# signal_interface2.net
KiCad netlist of a schematic drawn in EAGLE
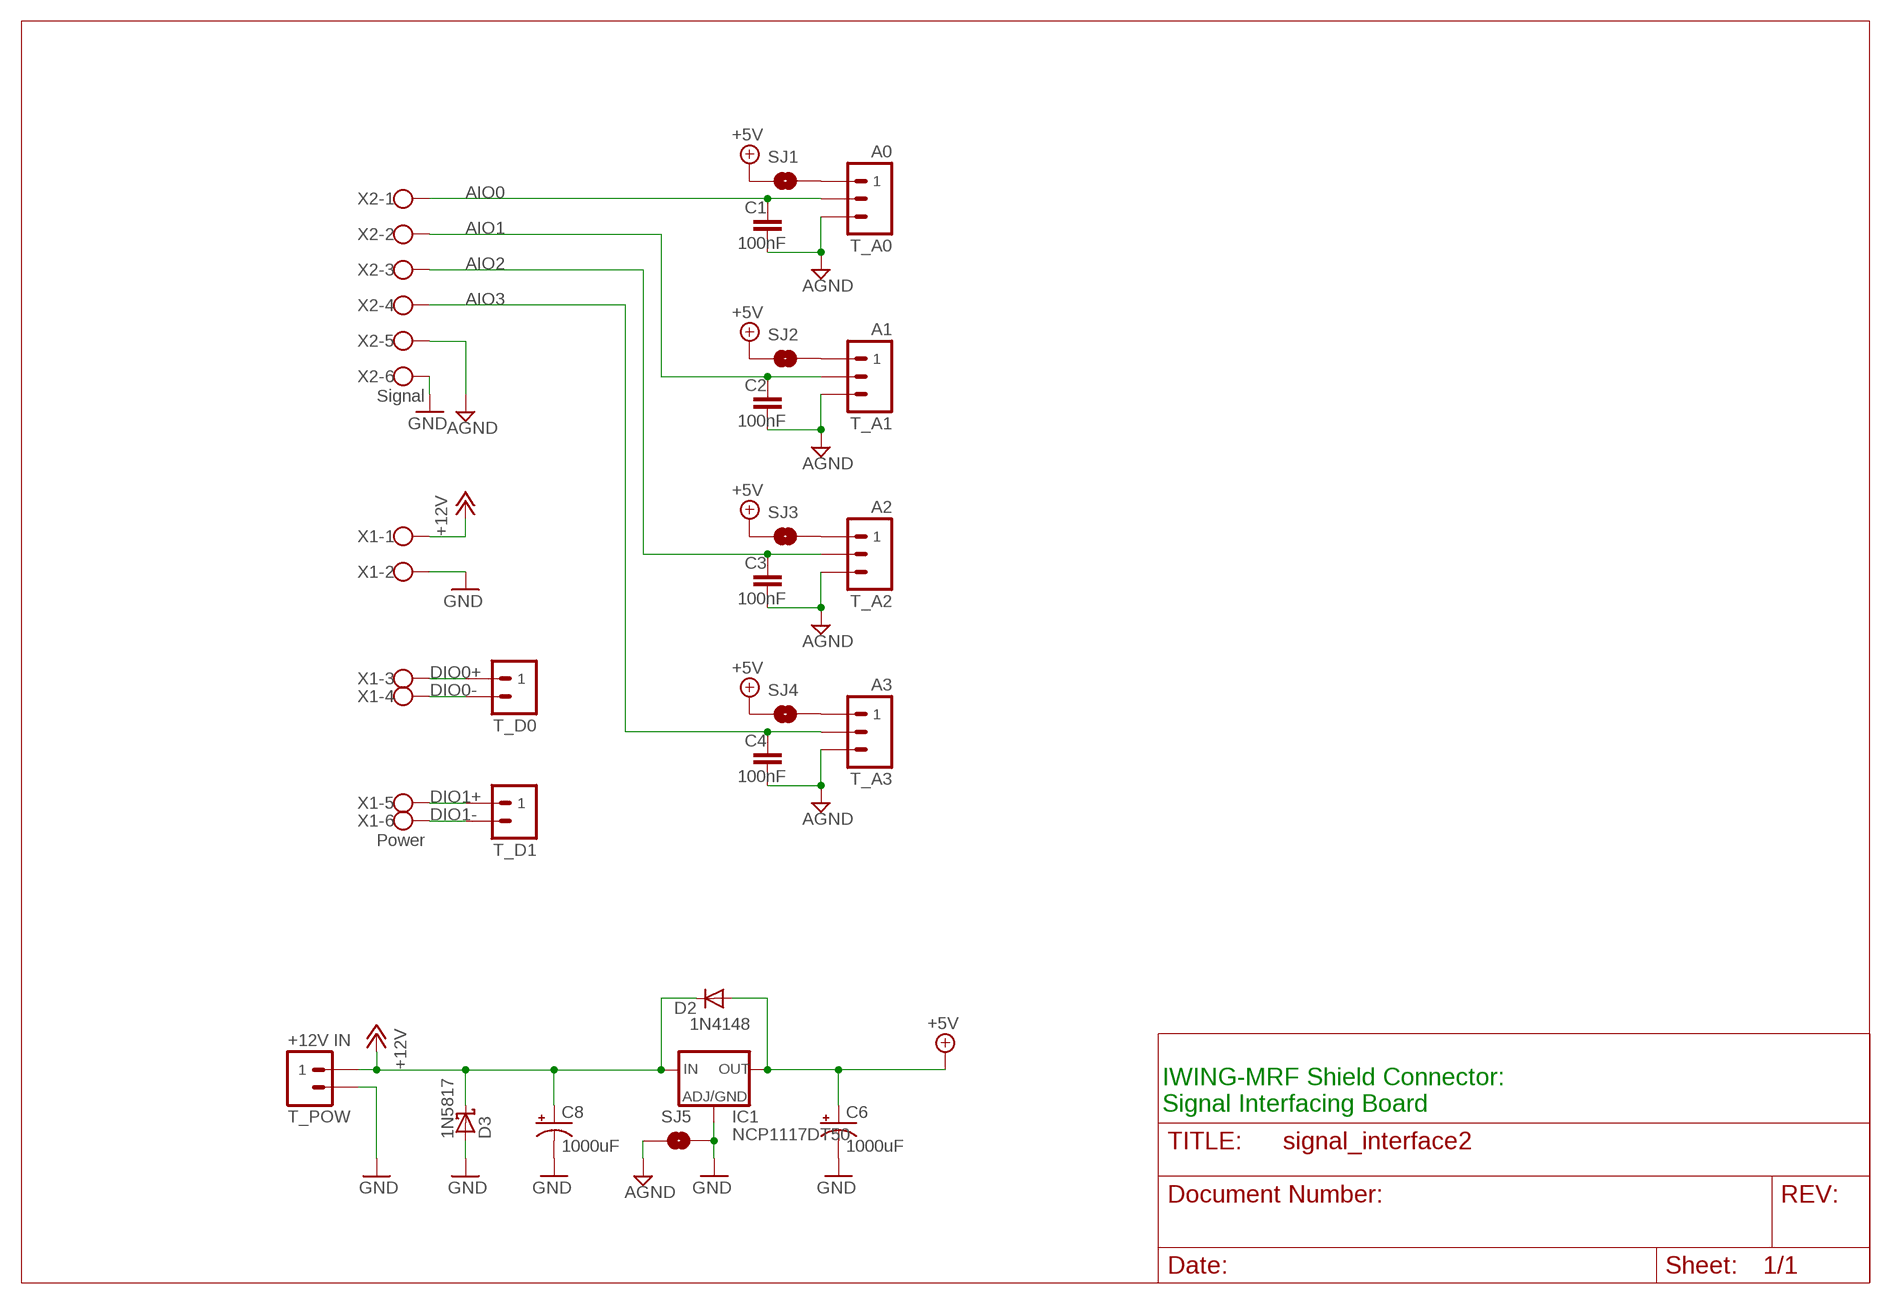
[diagram p0: schematic, sheet 1]

(export (version "E")
  (design (tool "Eeschema 10.0.6"))
  (components
    (comp (ref "C1")
      (value "100nF")
      (footprint "eagle-import:RCL_C050-025X075")
      (libsource (lib "eagle-import") (part "RCL_C-EU050-025X075"))
    )
    (comp (ref "C2")
      (value "100nF")
      (footprint "eagle-import:RCL_C050-025X075")
      (libsource (lib "eagle-import") (part "RCL_C-EU050-025X075"))
    )
    (comp (ref "C3")
      (value "100nF")
      (footprint "eagle-import:RCL_C050-025X075")
      (libsource (lib "eagle-import") (part "RCL_C-EU050-025X075"))
    )
    (comp (ref "C4")
      (value "100nF")
      (footprint "eagle-import:RCL_C050-025X075")
      (libsource (lib "eagle-import") (part "RCL_C-EU050-025X075"))
    )
    (comp (ref "C6")
      (value "1000uF")
      (footprint "eagle-import:RCL_E5-13")
      (libsource (lib "eagle-import") (part "RCL_CPOL-USE5-13"))
    )
    (comp (ref "C8")
      (value "1000uF")
      (footprint "eagle-import:RCL_E5-13")
      (libsource (lib "eagle-import") (part "RCL_CPOL-USE5-13"))
    )
    (comp (ref "D2")
      (value "1N4148")
      (footprint "eagle-import:DO35-100V")
      (libsource (lib "eagle-import") (part "1N4148-V"))
    )
    (comp (ref "D3")
      (value "1N5817")
      (footprint "eagle-import:DO41-150V")
      (libsource (lib "eagle-import") (part "1N5819-V"))
    )
    (comp (ref "IC1")
      (value "NCP1117DT50")
      (footprint "eagle-import:DPACK")
      (libsource (lib "eagle-import") (part "NCP1117?DT50"))
    )
    (comp (ref "SJ1")
      (value "SOLDERJUMPERNC")
      (footprint "eagle-import:SJ_2S")
      (libsource (lib "eagle-import") (part "SOLDERJUMPERNC"))
    )
    (comp (ref "SJ2")
      (value "SOLDERJUMPERNC")
      (footprint "eagle-import:SJ_2S")
      (libsource (lib "eagle-import") (part "SOLDERJUMPERNC"))
    )
    (comp (ref "SJ3")
      (value "SOLDERJUMPERNC")
      (footprint "eagle-import:SJ_2S")
      (libsource (lib "eagle-import") (part "SOLDERJUMPERNC"))
    )
    (comp (ref "SJ4")
      (value "SOLDERJUMPERNC")
      (footprint "eagle-import:SJ_2S")
      (libsource (lib "eagle-import") (part "SOLDERJUMPERNC"))
    )
    (comp (ref "SJ5")
      (value "SOLDERJUMPERTRACE")
      (footprint "eagle-import:SJ_2S-TRACE")
      (libsource (lib "eagle-import") (part "SOLDERJUMPERTRACE"))
    )
    (comp (ref "T_A0")
      (value "A0")
      (footprint "eagle-import:EK500V-03P")
      (libsource (lib "eagle-import") (part "ST03-5MM"))
    )
    (comp (ref "T_A1")
      (value "A1")
      (footprint "eagle-import:EK500V-03P")
      (libsource (lib "eagle-import") (part "ST03-5MM"))
    )
    (comp (ref "T_A2")
      (value "A2")
      (footprint "eagle-import:EK500V-03P")
      (libsource (lib "eagle-import") (part "ST03-5MM"))
    )
    (comp (ref "T_A3")
      (value "A3")
      (footprint "eagle-import:EK500V-03P")
      (libsource (lib "eagle-import") (part "ST03-5MM"))
    )
    (comp (ref "T_D0")
      (value "ST02-5MM")
      (footprint "eagle-import:EK500V-02P")
      (libsource (lib "eagle-import") (part "ST02-5MM"))
    )
    (comp (ref "T_D1")
      (value "ST02-5MM")
      (footprint "eagle-import:EK500V-02P")
      (libsource (lib "eagle-import") (part "ST02-5MM"))
    )
    (comp (ref "T_POW")
      (value "+12V IN")
      (footprint "eagle-import:EK500V-02P")
      (libsource (lib "eagle-import") (part "ST02-5MM"))
    )
    (comp (ref "X1")
      (value "Power")
      (footprint "eagle-import:5EHDRC-6P")
      (libsource (lib "eagle-import") (part "5EHDRC-6P"))
    )
    (comp (ref "X2")
      (value "Signal")
      (footprint "eagle-import:5EHDRC-6P")
      (libsource (lib "eagle-import") (part "5EHDRC-6P"))
    )
  )
  (nets
    (net (code "1") (name "+5V") (class "Default")
      (node (ref "C6") (pin "+") (pinfunction "+_+") (pintype "passive"))
      (node (ref "D2") (pin "A") (pinfunction "A_A") (pintype "passive"))
      (node (ref "IC1") (pin "4") (pinfunction "OUT_4") (pintype "passive"))
      (node (ref "SJ1") (pin "1") (pinfunction "1_1") (pintype "passive"))
      (node (ref "SJ2") (pin "1") (pinfunction "1_1") (pintype "passive"))
      (node (ref "SJ3") (pin "1") (pinfunction "1_1") (pintype "passive"))
      (node (ref "SJ4") (pin "1") (pinfunction "1_1") (pintype "passive"))
    )
    (net (code "2") (name "+12V") (class "Default")
      (node (ref "C8") (pin "+") (pinfunction "+_+") (pintype "passive"))
      (node (ref "D2") (pin "C") (pinfunction "C_C") (pintype "passive"))
      (node (ref "D3") (pin "C") (pinfunction "C_C") (pintype "passive"))
      (node (ref "IC1") (pin "3") (pinfunction "IN_3") (pintype "input"))
      (node (ref "T_POW") (pin "P$1") (pinfunction "1_P$1") (pintype "passive"))
      (node (ref "X1") (pin "1") (pinfunction "KL_1") (pintype "passive"))
    )
    (net (code "3") (name "/AIO0") (class "Default")
      (node (ref "C1") (pin "1") (pinfunction "1_1") (pintype "passive"))
      (node (ref "T_A0") (pin "P$2") (pinfunction "2_P$2") (pintype "passive"))
      (node (ref "X2") (pin "1") (pinfunction "KL_1") (pintype "passive"))
    )
    (net (code "4") (name "/AIO1") (class "Default")
      (node (ref "C2") (pin "1") (pinfunction "1_1") (pintype "passive"))
      (node (ref "T_A1") (pin "P$2") (pinfunction "2_P$2") (pintype "passive"))
      (node (ref "X2") (pin "2") (pinfunction "KL_2") (pintype "passive"))
    )
    (net (code "5") (name "/AIO2") (class "Default")
      (node (ref "C3") (pin "1") (pinfunction "1_1") (pintype "passive"))
      (node (ref "T_A2") (pin "P$2") (pinfunction "2_P$2") (pintype "passive"))
      (node (ref "X2") (pin "3") (pinfunction "KL_3") (pintype "passive"))
    )
    (net (code "6") (name "/AIO3") (class "Default")
      (node (ref "C4") (pin "1") (pinfunction "1_1") (pintype "passive"))
      (node (ref "T_A3") (pin "P$2") (pinfunction "2_P$2") (pintype "passive"))
      (node (ref "X2") (pin "4") (pinfunction "KL_4") (pintype "passive"))
    )
    (net (code "7") (name "/DIO0+") (class "Default")
      (node (ref "T_D0") (pin "P$1") (pinfunction "1_P$1") (pintype "passive"))
      (node (ref "X1") (pin "3") (pinfunction "KL_3") (pintype "passive"))
    )
    (net (code "8") (name "/DIO0-") (class "Default")
      (node (ref "T_D0") (pin "P$2") (pinfunction "2_P$2") (pintype "passive"))
      (node (ref "X1") (pin "4") (pinfunction "KL_4") (pintype "passive"))
    )
    (net (code "9") (name "/DIO1+") (class "Default")
      (node (ref "T_D1") (pin "P$1") (pinfunction "1_P$1") (pintype "passive"))
      (node (ref "X1") (pin "5") (pinfunction "KL_5") (pintype "passive"))
    )
    (net (code "10") (name "/DIO1-") (class "Default")
      (node (ref "T_D1") (pin "P$2") (pinfunction "2_P$2") (pintype "passive"))
      (node (ref "X1") (pin "6") (pinfunction "KL_6") (pintype "passive"))
    )
    (net (code "11") (name "AGND") (class "Default")
      (node (ref "C1") (pin "2") (pinfunction "2_2") (pintype "passive"))
      (node (ref "C2") (pin "2") (pinfunction "2_2") (pintype "passive"))
      (node (ref "C3") (pin "2") (pinfunction "2_2") (pintype "passive"))
      (node (ref "C4") (pin "2") (pinfunction "2_2") (pintype "passive"))
      (node (ref "SJ5") (pin "1") (pinfunction "1_1") (pintype "passive"))
      (node (ref "T_A0") (pin "P$3") (pinfunction "3_P$3") (pintype "passive"))
      (node (ref "T_A1") (pin "P$3") (pinfunction "3_P$3") (pintype "passive"))
      (node (ref "T_A2") (pin "P$3") (pinfunction "3_P$3") (pintype "passive"))
      (node (ref "T_A3") (pin "P$3") (pinfunction "3_P$3") (pintype "passive"))
      (node (ref "X2") (pin "5") (pinfunction "KL_5") (pintype "passive"))
    )
    (net (code "12") (name "GND") (class "Default")
      (node (ref "C6") (pin "-") (pinfunction "-_-") (pintype "passive"))
      (node (ref "C8") (pin "-") (pinfunction "-_-") (pintype "passive"))
      (node (ref "D3") (pin "A") (pinfunction "A_A") (pintype "passive"))
      (node (ref "IC1") (pin "1") (pinfunction "ADJ_1") (pintype "input"))
      (node (ref "SJ5") (pin "2") (pinfunction "2_2") (pintype "passive"))
      (node (ref "T_POW") (pin "P$2") (pinfunction "2_P$2") (pintype "passive"))
      (node (ref "X1") (pin "2") (pinfunction "KL_2") (pintype "passive"))
      (node (ref "X2") (pin "6") (pinfunction "KL_6") (pintype "passive"))
    )
    (net (code "13") (name "Net-(T_A0-1)") (class "Default")
      (node (ref "SJ1") (pin "2") (pinfunction "2_2") (pintype "passive"))
      (node (ref "T_A0") (pin "P$1") (pinfunction "1_P$1") (pintype "passive"))
    )
    (net (code "14") (name "Net-(T_A1-1)") (class "Default")
      (node (ref "SJ2") (pin "2") (pinfunction "2_2") (pintype "passive"))
      (node (ref "T_A1") (pin "P$1") (pinfunction "1_P$1") (pintype "passive"))
    )
    (net (code "15") (name "Net-(T_A2-1)") (class "Default")
      (node (ref "SJ3") (pin "2") (pinfunction "2_2") (pintype "passive"))
      (node (ref "T_A2") (pin "P$1") (pinfunction "1_P$1") (pintype "passive"))
    )
    (net (code "16") (name "Net-(T_A3-1)") (class "Default")
      (node (ref "SJ4") (pin "2") (pinfunction "2_2") (pintype "passive"))
      (node (ref "T_A3") (pin "P$1") (pinfunction "1_P$1") (pintype "passive"))
    )
  )
)
